# NG2092_LEVEL_SHIFT.net
KiCad netlist of a schematic drawn in Altium Designer
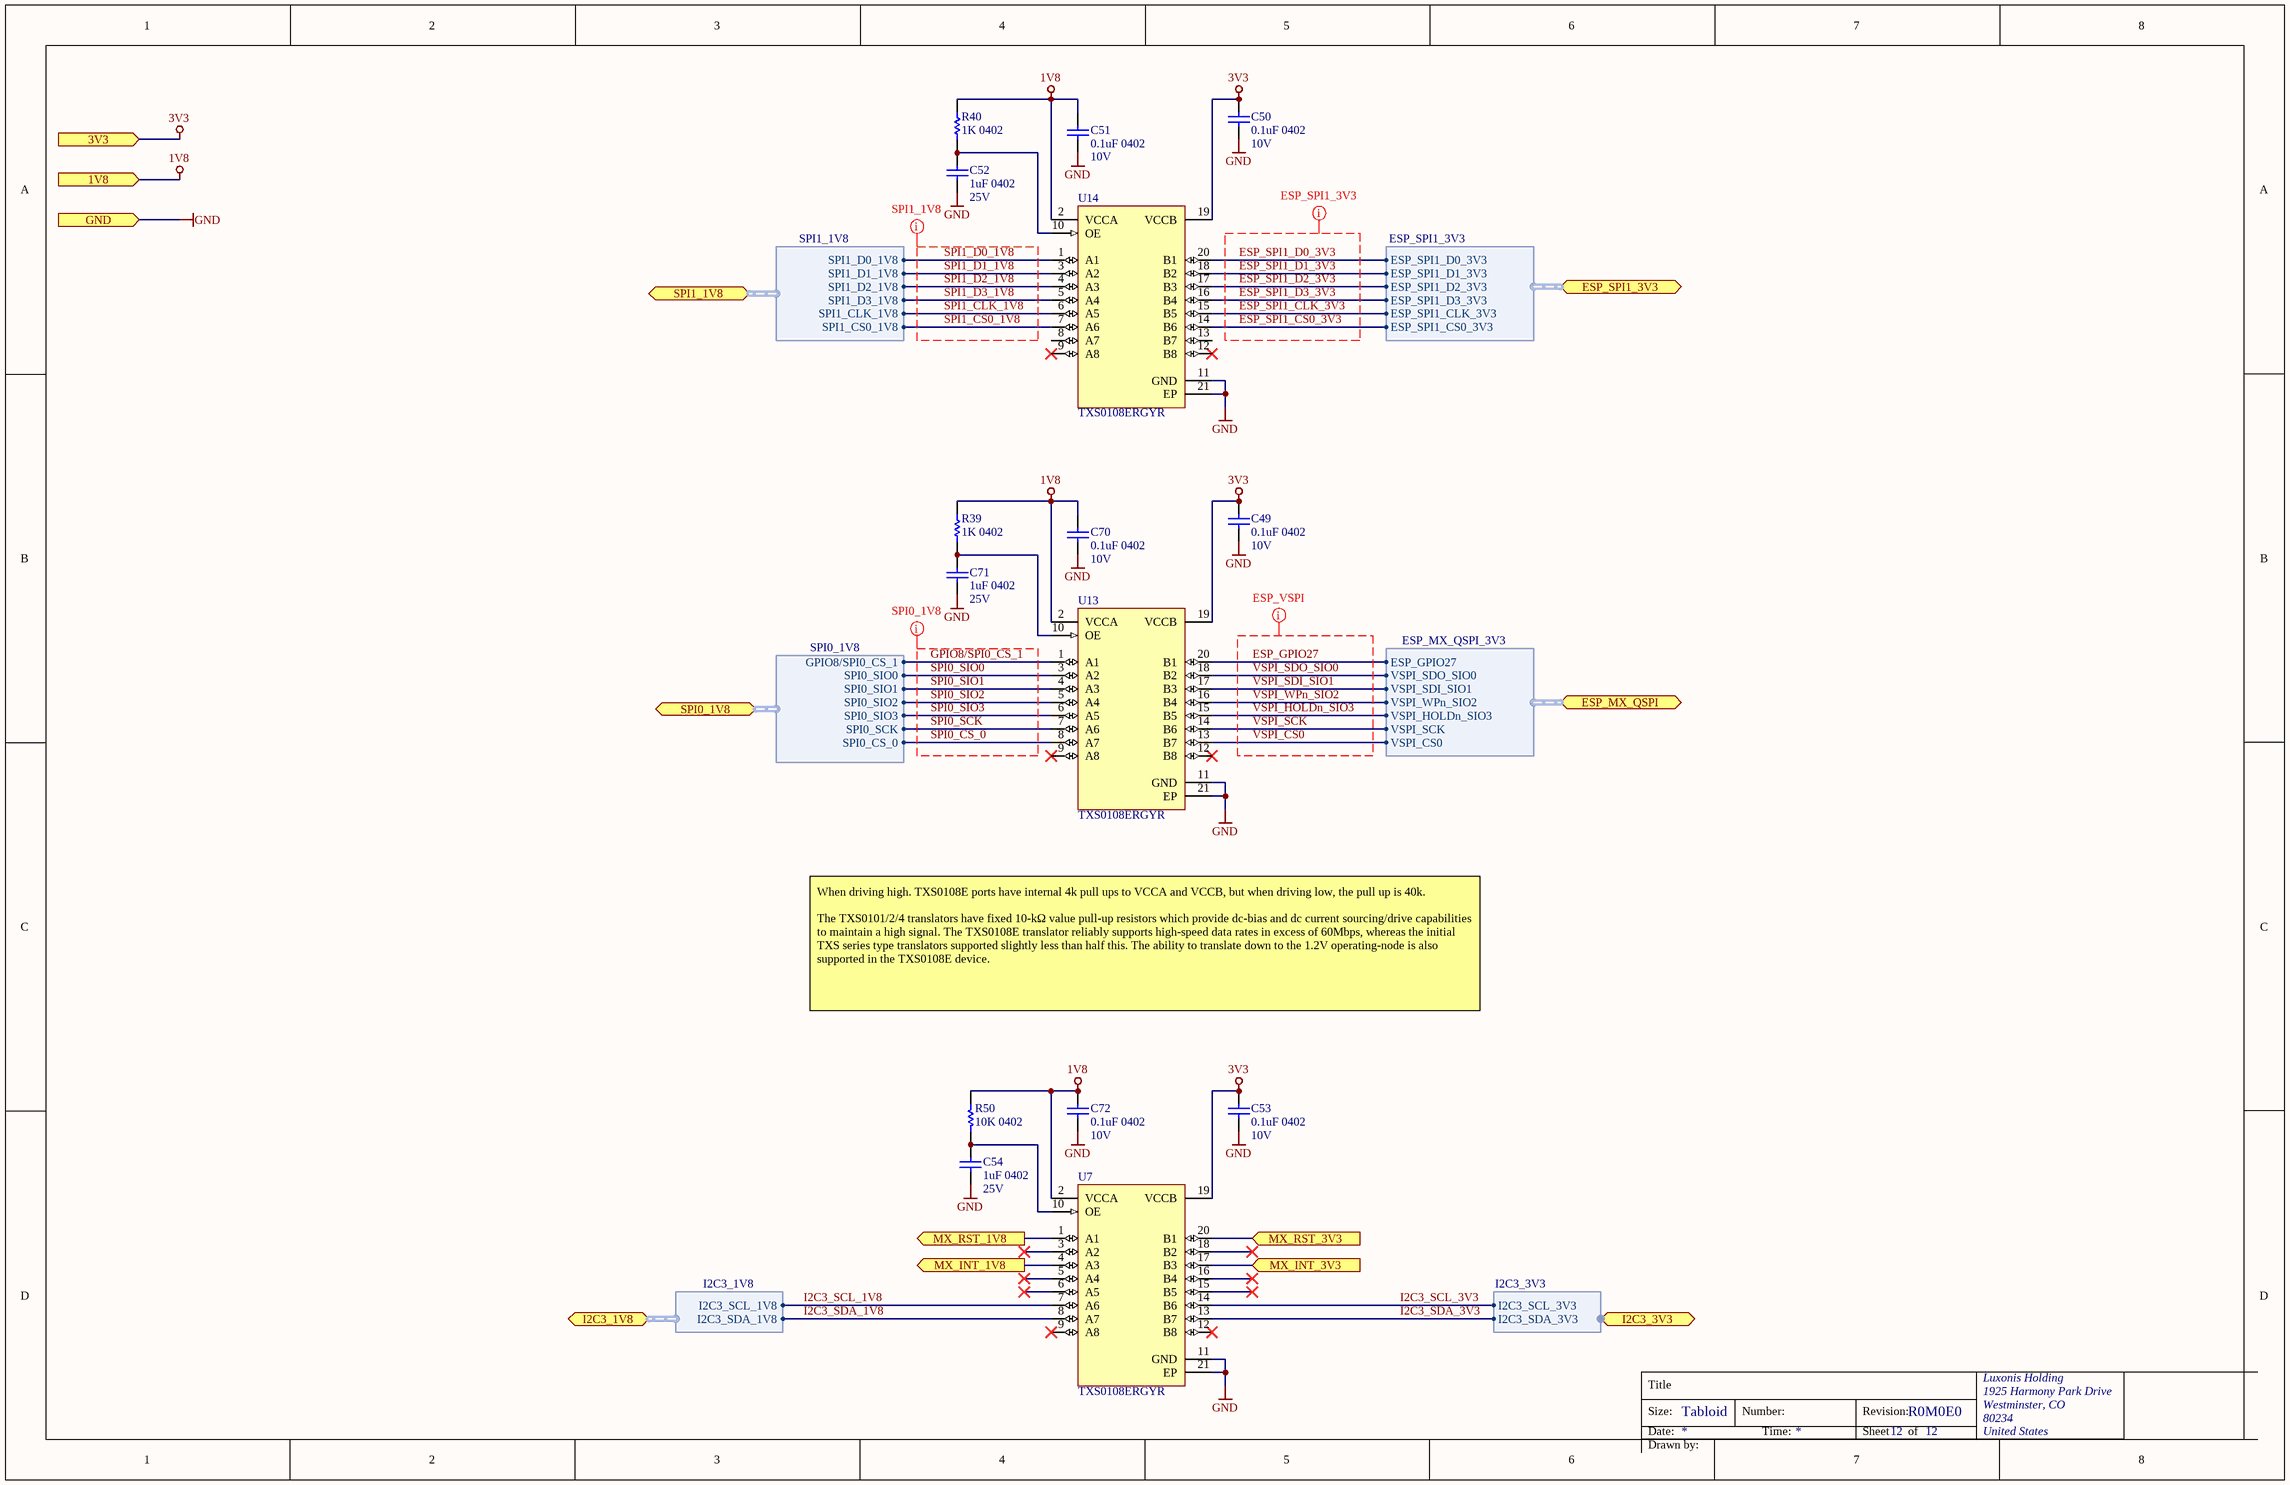
[diagram p0: NG2092_LEVEL_SHIFT.SchDoc]

(export (version "E")
  (design (tool "Eeschema 10.0.6"))
  (components
    (comp (ref "C49")
      (value "0.1uF 0402")
      (footprint "CAP_Altium_Vault_Generic:CAPC0402(1005)70_L")
      (description "CAP CER 0.1UF 10V X7R 0402 5%")
      (fields (field (name "TOLERANCE") "5%") (field (name "VOLTAGE RATING") "10V"))
      (libsource (lib "LuxonisMaster") (part "GRM155R71A104JA01D"))
    )
    (comp (ref "C50")
      (value "0.1uF 0402")
      (footprint "CAP_Altium_Vault_Generic:CAPC0402(1005)70_L")
      (description "CAP CER 0.1UF 10V X7R 0402 5%")
      (fields (field (name "TOLERANCE") "5%") (field (name "VOLTAGE RATING") "10V"))
      (libsource (lib "LuxonisMaster") (part "GRM155R71A104JA01D"))
    )
    (comp (ref "C51")
      (value "0.1uF 0402")
      (footprint "CAP_Altium_Vault_Generic:CAPC0402(1005)70_L")
      (description "CAP CER 0.1UF 10V X7R 0402 5%")
      (fields (field (name "TOLERANCE") "5%") (field (name "VOLTAGE RATING") "10V"))
      (libsource (lib "LuxonisMaster") (part "GRM155R71A104JA01D"))
    )
    (comp (ref "C52")
      (value "1uF 0402")
      (footprint "CAP_Altium_Vault_Generic:CAPC0402(1005)70_N")
      (description "CAP CER 1UF 25V X5R 0402 10%")
      (fields
        (field (name "TOLERANCE") "10%")
        (field (name "VOLTAGE") "25V")
        (field (name "VOLTAGE RATING") "25V")
      )
      (libsource (lib "LuxonisMaster") (part "GRM155R61E105KA12D"))
    )
    (comp (ref "C53")
      (value "0.1uF 0402")
      (footprint "CAP_Altium_Vault_Generic:CAPC0402(1005)70_L")
      (description "CAP CER 0.1UF 10V X7R 0402 5%")
      (fields (field (name "TOLERANCE") "5%") (field (name "VOLTAGE RATING") "10V"))
      (libsource (lib "LuxonisMaster") (part "GRM155R71A104JA01D"))
    )
    (comp (ref "C54")
      (value "1uF 0402")
      (footprint "CAP_Altium_Vault_Generic:CAPC0402(1005)70_N")
      (description "CAP CER 1UF 25V X5R 0402 10%")
      (fields
        (field (name "TOLERANCE") "10%")
        (field (name "VOLTAGE") "25V")
        (field (name "VOLTAGE RATING") "25V")
      )
      (libsource (lib "LuxonisMaster") (part "GRM155R61E105KA12D"))
    )
    (comp (ref "C70")
      (value "0.1uF 0402")
      (footprint "CAP_Altium_Vault_Generic:CAPC0402(1005)70_L")
      (description "CAP CER 0.1UF 10V X7R 0402 5%")
      (fields (field (name "TOLERANCE") "5%") (field (name "VOLTAGE RATING") "10V"))
      (libsource (lib "LuxonisMaster") (part "GRM155R71A104JA01D"))
    )
    (comp (ref "C71")
      (value "1uF 0402")
      (footprint "CAP_Altium_Vault_Generic:CAPC0402(1005)70_N")
      (description "CAP CER 1UF 25V X5R 0402 10%")
      (fields
        (field (name "TOLERANCE") "10%")
        (field (name "VOLTAGE") "25V")
        (field (name "VOLTAGE RATING") "25V")
      )
      (libsource (lib "LuxonisMaster") (part "GRM155R61E105KA12D"))
    )
    (comp (ref "C72")
      (value "0.1uF 0402")
      (footprint "CAP_Altium_Vault_Generic:CAPC0402(1005)70_L")
      (description "CAP CER 0.1UF 10V X7R 0402 5%")
      (fields (field (name "TOLERANCE") "5%") (field (name "VOLTAGE RATING") "10V"))
      (libsource (lib "LuxonisMaster") (part "GRM155R71A104JA01D"))
    )
    (comp (ref "R39")
      (value "1K 0402")
      (footprint "RES_Altium_Vault_Generic:RESC0402(1005)_L")
      (description "RES SMD 1K OHM 1% 1/16W 0402")
      (fields (field (name "TOLERANCE") "1%"))
      (libsource (lib "LuxonisMaster") (part "RC0402FR-071KL"))
    )
    (comp (ref "R40")
      (value "1K 0402")
      (footprint "RES_Altium_Vault_Generic:RESC0402(1005)_L")
      (description "RES SMD 1K OHM 1% 1/16W 0402")
      (fields (field (name "TOLERANCE") "1%"))
      (libsource (lib "LuxonisMaster") (part "RC0402FR-071KL"))
    )
    (comp (ref "R50")
      (value "10K 0402")
      (footprint "RES_Altium_Vault_Generic:RESC0402(1005)_L")
      (fields (field (name "TOLERANCE") "1%"))
      (libsource (lib "LuxonisMaster") (part "RC0402FR-1310KL"))
    )
    (comp (ref "U7")
      (value "TXS0108ERGYR")
      (footprint "LuxonisMaster:TXS0108ERGYR")
      (description "IC TRNSLTR BIDIRECTIONAL 20VQFN")
      (libsource (lib "LuxonisMaster") (part "TXS0108ERGYR"))
    )
    (comp (ref "U13")
      (value "TXS0108ERGYR")
      (footprint "LuxonisMaster:TXS0108ERGYR")
      (description "IC TRNSLTR BIDIRECTIONAL 20VQFN")
      (libsource (lib "LuxonisMaster") (part "TXS0108ERGYR"))
    )
    (comp (ref "U14")
      (value "TXS0108ERGYR")
      (footprint "LuxonisMaster:TXS0108ERGYR")
      (description "IC TRNSLTR BIDIRECTIONAL 20VQFN")
      (libsource (lib "LuxonisMaster") (part "TXS0108ERGYR"))
    )
  )
  (nets
    (net (code "7") (name "/ESP_GPIO27") (class "Default")
      (node (ref "U13") (pin "20") (pinfunction "B1_20") (pintype "bidirectional"))
    )
    (net (code "8") (name "/ESP_SPI1_CLK_3V3") (class "Default")
      (node (ref "U14") (pin "15") (pinfunction "B5_15") (pintype "bidirectional"))
    )
    (net (code "9") (name "/ESP_SPI1_CS0_3V3") (class "Default")
      (node (ref "U14") (pin "14") (pinfunction "B6_14") (pintype "bidirectional"))
    )
    (net (code "10") (name "/ESP_SPI1_D0_3V3") (class "Default")
      (node (ref "U14") (pin "20") (pinfunction "B1_20") (pintype "bidirectional"))
    )
    (net (code "11") (name "/ESP_SPI1_D1_3V3") (class "Default")
      (node (ref "U14") (pin "18") (pinfunction "B2_18") (pintype "bidirectional"))
    )
    (net (code "12") (name "/ESP_SPI1_D2_3V3") (class "Default")
      (node (ref "U14") (pin "17") (pinfunction "B3_17") (pintype "bidirectional"))
    )
    (net (code "13") (name "/ESP_SPI1_D3_3V3") (class "Default")
      (node (ref "U14") (pin "16") (pinfunction "B4_16") (pintype "bidirectional"))
    )
    (net (code "14") (name "/GPIO8{slash}SPI0_CS_1") (class "Default")
      (node (ref "U13") (pin "1") (pinfunction "A1_1") (pintype "bidirectional"))
    )
    (net (code "15") (name "/I2C3_SCL_1V8") (class "Default")
      (node (ref "U7") (pin "7") (pinfunction "A6_7") (pintype "bidirectional"))
    )
    (net (code "16") (name "/I2C3_SCL_3V3") (class "Default")
      (node (ref "U7") (pin "14") (pinfunction "B6_14") (pintype "bidirectional"))
    )
    (net (code "17") (name "/I2C3_SDA_1V8") (class "Default")
      (node (ref "U7") (pin "8") (pinfunction "A7_8") (pintype "bidirectional"))
    )
    (net (code "18") (name "/I2C3_SDA_3V3") (class "Default")
      (node (ref "U7") (pin "13") (pinfunction "B7_13") (pintype "bidirectional"))
    )
    (net (code "19") (name "/MX_INT_1V8") (class "Default")
      (node (ref "U7") (pin "4") (pinfunction "A3_4") (pintype "bidirectional"))
    )
    (net (code "20") (name "/MX_INT_3V3") (class "Default")
      (node (ref "U7") (pin "17") (pinfunction "B3_17") (pintype "bidirectional"))
    )
    (net (code "21") (name "/MX_RST_1V8") (class "Default")
      (node (ref "U7") (pin "1") (pinfunction "A1_1") (pintype "bidirectional"))
    )
    (net (code "22") (name "/MX_RST_3V3") (class "Default")
      (node (ref "U7") (pin "20") (pinfunction "B1_20") (pintype "bidirectional"))
    )
    (net (code "23") (name "/SPI0_CS_0") (class "Default")
      (node (ref "U13") (pin "8") (pinfunction "A7_8") (pintype "bidirectional"))
    )
    (net (code "24") (name "/SPI0_SCK") (class "Default")
      (node (ref "U13") (pin "7") (pinfunction "A6_7") (pintype "bidirectional"))
    )
    (net (code "25") (name "/SPI0_SIO0") (class "Default")
      (node (ref "U13") (pin "3") (pinfunction "A2_3") (pintype "bidirectional"))
    )
    (net (code "26") (name "/SPI0_SIO1") (class "Default")
      (node (ref "U13") (pin "4") (pinfunction "A3_4") (pintype "bidirectional"))
    )
    (net (code "27") (name "/SPI0_SIO2") (class "Default")
      (node (ref "U13") (pin "5") (pinfunction "A4_5") (pintype "bidirectional"))
    )
    (net (code "28") (name "/SPI0_SIO3") (class "Default")
      (node (ref "U13") (pin "6") (pinfunction "A5_6") (pintype "bidirectional"))
    )
    (net (code "29") (name "/SPI1_CLK_1V8") (class "Default")
      (node (ref "U14") (pin "6") (pinfunction "A5_6") (pintype "bidirectional"))
    )
    (net (code "30") (name "/SPI1_CS0_1V8") (class "Default")
      (node (ref "U14") (pin "7") (pinfunction "A6_7") (pintype "bidirectional"))
    )
    (net (code "31") (name "/SPI1_D0_1V8") (class "Default")
      (node (ref "U14") (pin "1") (pinfunction "A1_1") (pintype "bidirectional"))
    )
    (net (code "32") (name "/SPI1_D1_1V8") (class "Default")
      (node (ref "U14") (pin "3") (pinfunction "A2_3") (pintype "bidirectional"))
    )
    (net (code "33") (name "/SPI1_D2_1V8") (class "Default")
      (node (ref "U14") (pin "4") (pinfunction "A3_4") (pintype "bidirectional"))
    )
    (net (code "34") (name "/SPI1_D3_1V8") (class "Default")
      (node (ref "U14") (pin "5") (pinfunction "A4_5") (pintype "bidirectional"))
    )
    (net (code "35") (name "/VSPI_CS0") (class "Default")
      (node (ref "U13") (pin "13") (pinfunction "B7_13") (pintype "bidirectional"))
    )
    (net (code "36") (name "/VSPI_HOLDn_SIO3") (class "Default")
      (node (ref "U13") (pin "15") (pinfunction "B5_15") (pintype "bidirectional"))
    )
    (net (code "37") (name "/VSPI_SCK") (class "Default")
      (node (ref "U13") (pin "14") (pinfunction "B6_14") (pintype "bidirectional"))
    )
    (net (code "38") (name "/VSPI_SDI_SIO1") (class "Default")
      (node (ref "U13") (pin "17") (pinfunction "B3_17") (pintype "bidirectional"))
    )
    (net (code "39") (name "/VSPI_SDO_SIO0") (class "Default")
      (node (ref "U13") (pin "18") (pinfunction "B2_18") (pintype "bidirectional"))
    )
    (net (code "40") (name "/VSPI_WPn_SIO2") (class "Default")
      (node (ref "U13") (pin "16") (pinfunction "B4_16") (pintype "bidirectional"))
    )
    (net (code "47") (name "1V8") (class "Default")
      (node (ref "C51") (pin "2") (pinfunction "2_2") (pintype "passive"))
      (node (ref "C70") (pin "2") (pinfunction "2_2") (pintype "passive"))
      (node (ref "C72") (pin "2") (pinfunction "2_2") (pintype "passive"))
      (node (ref "R39") (pin "2") (pinfunction "2_2") (pintype "passive"))
      (node (ref "R40") (pin "2") (pinfunction "2_2") (pintype "passive"))
      (node (ref "R50") (pin "1") (pinfunction "1_1") (pintype "passive"))
      (node (ref "U13") (pin "2") (pinfunction "VCCA_2") (pintype "power_in"))
      (node (ref "U14") (pin "2") (pinfunction "VCCA_2") (pintype "power_in"))
      (node (ref "U7") (pin "2") (pinfunction "VCCA_2") (pintype "power_in"))
    )
    (net (code "48") (name "3V3") (class "Default")
      (node (ref "C49") (pin "2") (pinfunction "2_2") (pintype "passive"))
      (node (ref "C50") (pin "2") (pinfunction "2_2") (pintype "passive"))
      (node (ref "C53") (pin "2") (pinfunction "2_2") (pintype "passive"))
      (node (ref "U13") (pin "19") (pinfunction "VCCB_19") (pintype "power_in"))
      (node (ref "U14") (pin "19") (pinfunction "VCCB_19") (pintype "power_in"))
      (node (ref "U7") (pin "19") (pinfunction "VCCB_19") (pintype "power_in"))
    )
    (net (code "49") (name "GND") (class "Default")
      (node (ref "C49") (pin "1") (pinfunction "1_1") (pintype "passive"))
      (node (ref "C50") (pin "1") (pinfunction "1_1") (pintype "passive"))
      (node (ref "C51") (pin "1") (pinfunction "1_1") (pintype "passive"))
      (node (ref "C52") (pin "1") (pinfunction "1_1") (pintype "passive"))
      (node (ref "C53") (pin "1") (pinfunction "1_1") (pintype "passive"))
      (node (ref "C54") (pin "1") (pinfunction "1_1") (pintype "passive"))
      (node (ref "C70") (pin "1") (pinfunction "1_1") (pintype "passive"))
      (node (ref "C71") (pin "1") (pinfunction "1_1") (pintype "passive"))
      (node (ref "C72") (pin "1") (pinfunction "1_1") (pintype "passive"))
      (node (ref "U13") (pin "11") (pinfunction "GND_11") (pintype "power_in"))
      (node (ref "U13") (pin "21") (pinfunction "EP_21") (pintype "power_in"))
      (node (ref "U14") (pin "11") (pinfunction "GND_11") (pintype "power_in"))
      (node (ref "U14") (pin "21") (pinfunction "EP_21") (pintype "power_in"))
      (node (ref "U7") (pin "11") (pinfunction "GND_11") (pintype "power_in"))
      (node (ref "U7") (pin "21") (pinfunction "EP_21") (pintype "power_in"))
    )
    (net (code "50") (name "Net-(U7-OE)") (class "Default")
      (node (ref "C54") (pin "2") (pinfunction "2_2") (pintype "passive"))
      (node (ref "R50") (pin "2") (pinfunction "2_2") (pintype "passive"))
      (node (ref "U7") (pin "10") (pinfunction "OE_10") (pintype "input"))
    )
    (net (code "51") (name "Net-(U13-OE)") (class "Default")
      (node (ref "C71") (pin "2") (pinfunction "2_2") (pintype "passive"))
      (node (ref "R39") (pin "1") (pinfunction "1_1") (pintype "passive"))
      (node (ref "U13") (pin "10") (pinfunction "OE_10") (pintype "input"))
    )
    (net (code "52") (name "Net-(U14-OE)") (class "Default")
      (node (ref "C52") (pin "2") (pinfunction "2_2") (pintype "passive"))
      (node (ref "R40") (pin "1") (pinfunction "1_1") (pintype "passive"))
      (node (ref "U14") (pin "10") (pinfunction "OE_10") (pintype "input"))
    )
    (net (code "53") (name "unconnected-(U7-A2-Pad3)") (class "Default")
      (node (ref "U7") (pin "3") (pinfunction "A2_3") (pintype "bidirectional+no_connect"))
    )
    (net (code "54") (name "unconnected-(U7-A4-Pad5)") (class "Default")
      (node (ref "U7") (pin "5") (pinfunction "A4_5") (pintype "bidirectional+no_connect"))
    )
    (net (code "55") (name "unconnected-(U7-A5-Pad6)") (class "Default")
      (node (ref "U7") (pin "6") (pinfunction "A5_6") (pintype "bidirectional+no_connect"))
    )
    (net (code "56") (name "unconnected-(U7-A8-Pad9)") (class "Default")
      (node (ref "U7") (pin "9") (pinfunction "A8_9") (pintype "bidirectional+no_connect"))
    )
    (net (code "57") (name "unconnected-(U7-B2-Pad18)") (class "Default")
      (node (ref "U7") (pin "18") (pinfunction "B2_18") (pintype "bidirectional+no_connect"))
    )
    (net (code "58") (name "unconnected-(U7-B4-Pad16)") (class "Default")
      (node (ref "U7") (pin "16") (pinfunction "B4_16") (pintype "bidirectional+no_connect"))
    )
    (net (code "59") (name "unconnected-(U7-B5-Pad15)") (class "Default")
      (node (ref "U7") (pin "15") (pinfunction "B5_15") (pintype "bidirectional+no_connect"))
    )
    (net (code "60") (name "unconnected-(U7-B8-Pad12)") (class "Default")
      (node (ref "U7") (pin "12") (pinfunction "B8_12") (pintype "bidirectional+no_connect"))
    )
    (net (code "61") (name "unconnected-(U13-A8-Pad9)") (class "Default")
      (node (ref "U13") (pin "9") (pinfunction "A8_9") (pintype "bidirectional+no_connect"))
    )
    (net (code "62") (name "unconnected-(U13-B8-Pad12)") (class "Default")
      (node (ref "U13") (pin "12") (pinfunction "B8_12") (pintype "bidirectional+no_connect"))
    )
    (net (code "63") (name "unconnected-(U14-A7-Pad8)") (class "Default")
      (node (ref "U14") (pin "8") (pinfunction "A7_8") (pintype "bidirectional"))
    )
    (net (code "64") (name "unconnected-(U14-A8-Pad9)") (class "Default")
      (node (ref "U14") (pin "9") (pinfunction "A8_9") (pintype "bidirectional+no_connect"))
    )
    (net (code "65") (name "unconnected-(U14-B7-Pad13)") (class "Default")
      (node (ref "U14") (pin "13") (pinfunction "B7_13") (pintype "bidirectional"))
    )
    (net (code "66") (name "unconnected-(U14-B8-Pad12)") (class "Default")
      (node (ref "U14") (pin "12") (pinfunction "B8_12") (pintype "bidirectional+no_connect"))
    )
  )
)
